# Qwiic_TMF8801.net
KiCad netlist of a schematic drawn in EAGLE
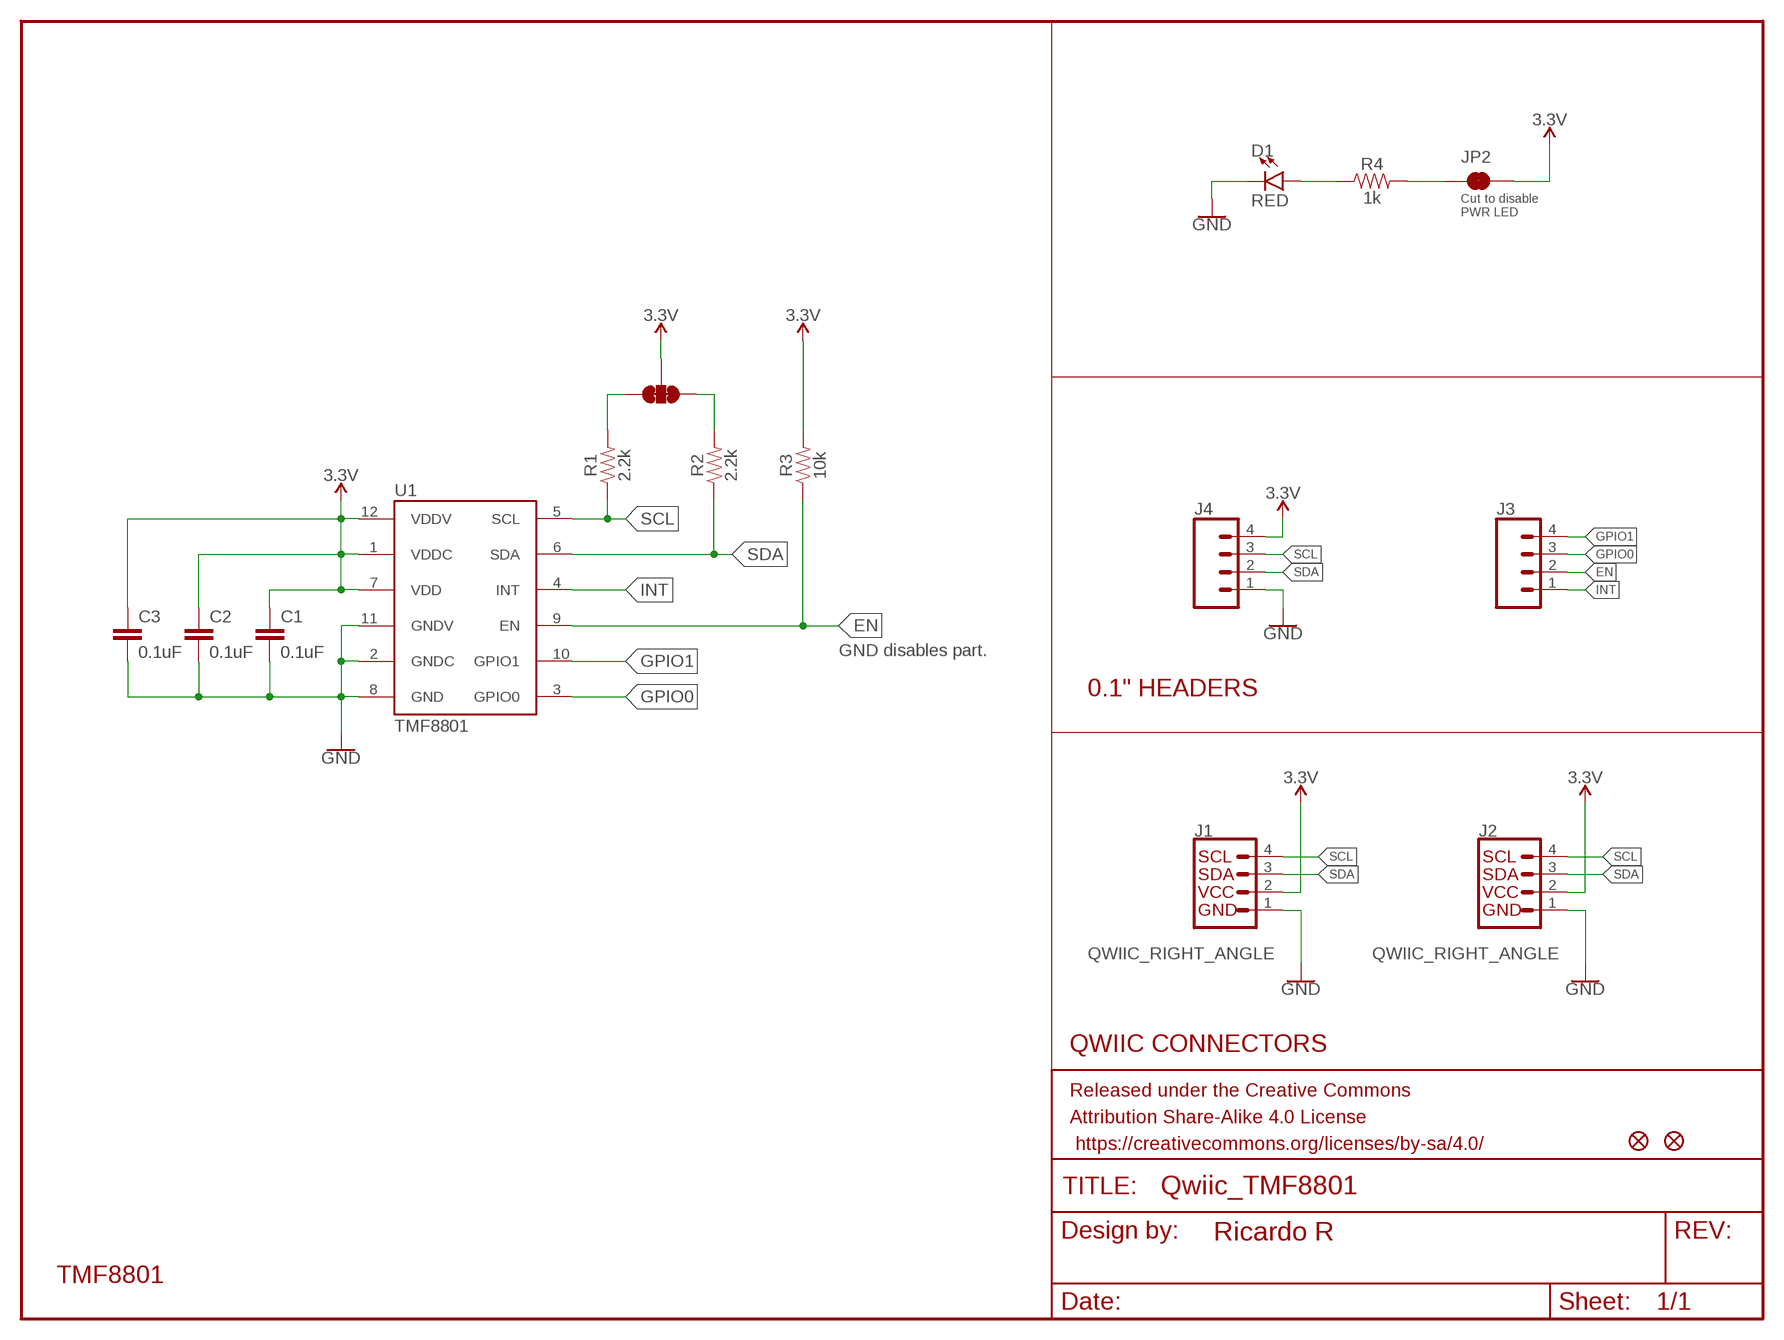
[diagram p0: schematic, sheet 1]

(export (version "E")
  (design (tool "Eeschema 10.0.6"))
  (components
    (comp (ref "C1")
      (value "0.1uF")
      (footprint "eagle-import:0603")
      (libsource (lib "eagle-import") (part "0.1UF-0603-25V-5%"))
    )
    (comp (ref "C2")
      (value "0.1uF")
      (footprint "eagle-import:0603")
      (libsource (lib "eagle-import") (part "0.1UF-0603-25V-5%"))
    )
    (comp (ref "C3")
      (value "0.1uF")
      (footprint "eagle-import:0603")
      (libsource (lib "eagle-import") (part "0.1UF-0603-25V-5%"))
    )
    (comp (ref "D1")
      (value "RED")
      (footprint "eagle-import:LED-0603")
      (libsource (lib "eagle-import") (part "LED-RED0603"))
    )
    (comp (ref "FD1")
      (value "FIDUCIAL1X2")
      (footprint "eagle-import:FIDUCIAL-1X2")
      (libsource (lib "eagle-import") (part "FIDUCIAL1X2"))
    )
    (comp (ref "FD2")
      (value "FIDUCIAL1X2")
      (footprint "eagle-import:FIDUCIAL-1X2")
      (libsource (lib "eagle-import") (part "FIDUCIAL1X2"))
    )
    (comp (ref "FRAME1")
      (value "FRAME-LETTERNO_PACKAGE")
      (footprint "eagle-import:DUMMY")
      (fields (field (name "DESIGNER") "Ricardo R") (field (name "DESIGNER_1") "Ricardo R"))
      (libsource (lib "eagle-import") (part "FRAME-LETTERNO_PACKAGE"))
    )
    (comp (ref "J1")
      (value "QWIIC_RIGHT_ANGLE")
      (footprint "eagle-import:1X04_1MM_RA")
      (libsource (lib "eagle-import") (part "QWIIC_CONNECTORJS-1MM"))
    )
    (comp (ref "J2")
      (value "QWIIC_RIGHT_ANGLE")
      (footprint "eagle-import:1X04_1MM_RA")
      (libsource (lib "eagle-import") (part "QWIIC_CONNECTORJS-1MM"))
    )
    (comp (ref "J3")
      (value "CONN_04")
      (footprint "eagle-import:1X04")
      (libsource (lib "eagle-import") (part "CONN_04"))
    )
    (comp (ref "J4")
      (value "CONN_04")
      (footprint "eagle-import:1X04")
      (libsource (lib "eagle-import") (part "CONN_04"))
    )
    (comp (ref "JP1")
      (value "JUMPER-SMT_3_2-NC_TRACE_SILK")
      (footprint "eagle-import:SMT-JUMPER_3_2-NC_TRACE_SILK")
      (libsource (lib "eagle-import") (part "JUMPER-SMT_3_2-NC_TRACE_SILK"))
    )
    (comp (ref "JP2")
      (value "JUMPER-SMT_2_NC_TRACE_SILK")
      (footprint "eagle-import:SMT-JUMPER_2_NC_TRACE_SILK")
      (libsource (lib "eagle-import") (part "JUMPER-SMT_2_NC_TRACE_SILK"))
    )
    (comp (ref "R1")
      (value "2.2k")
      (footprint "eagle-import:0603")
      (libsource (lib "eagle-import") (part "2.2KOHM-0603-1/10W-1%"))
    )
    (comp (ref "R2")
      (value "2.2k")
      (footprint "eagle-import:0603")
      (libsource (lib "eagle-import") (part "2.2KOHM-0603-1/10W-1%"))
    )
    (comp (ref "R3")
      (value "10k")
      (footprint "eagle-import:0603")
      (libsource (lib "eagle-import") (part "10KOHM-0603-1/10W-1%"))
    )
    (comp (ref "R4")
      (value "1k")
      (footprint "eagle-import:0603")
      (libsource (lib "eagle-import") (part "1KOHM-0603-1/10W-1%"))
    )
    (comp (ref "U1")
      (value "TMF8801")
      (footprint "eagle-import:TMF8801-CUSTOM")
      (libsource (lib "eagle-import") (part "TMF8801TMF8801"))
    )
  )
  (nets
    (net (code "1") (name "3.3V") (class "Default")
      (node (ref "C1") (pin "1") (pinfunction "1_1") (pintype "passive"))
      (node (ref "C2") (pin "1") (pinfunction "1_1") (pintype "passive"))
      (node (ref "C3") (pin "1") (pinfunction "1_1") (pintype "passive"))
      (node (ref "J1") (pin "2") (pinfunction "VCC_2") (pintype "power_in"))
      (node (ref "J2") (pin "2") (pinfunction "VCC_2") (pintype "power_in"))
      (node (ref "J4") (pin "4") (pinfunction "4_4") (pintype "passive"))
      (node (ref "JP1") (pin "2") (pinfunction "2_2") (pintype "passive"))
      (node (ref "JP2") (pin "2") (pinfunction "2_2") (pintype "passive"))
      (node (ref "R3") (pin "2") (pinfunction "2_2") (pintype "passive"))
      (node (ref "U1") (pin "1") (pinfunction "VDDC_1") (pintype "power_in"))
      (node (ref "U1") (pin "12") (pinfunction "VDDV_12") (pintype "power_in"))
      (node (ref "U1") (pin "7") (pinfunction "VDD_7") (pintype "power_in"))
    )
    (net (code "2") (name "EN") (class "Default")
      (node (ref "J3") (pin "2") (pinfunction "2_2") (pintype "passive"))
      (node (ref "R3") (pin "1") (pinfunction "1_1") (pintype "passive"))
      (node (ref "U1") (pin "9") (pinfunction "EN_9") (pintype "input"))
    )
    (net (code "3") (name "GND") (class "Default")
      (node (ref "C1") (pin "2") (pinfunction "2_2") (pintype "passive"))
      (node (ref "C2") (pin "2") (pinfunction "2_2") (pintype "passive"))
      (node (ref "C3") (pin "2") (pinfunction "2_2") (pintype "passive"))
      (node (ref "D1") (pin "C") (pinfunction "C_C") (pintype "passive"))
      (node (ref "J1") (pin "1") (pinfunction "GND_1") (pintype "power_in"))
      (node (ref "J2") (pin "1") (pinfunction "GND_1") (pintype "power_in"))
      (node (ref "J4") (pin "1") (pinfunction "1_1") (pintype "passive"))
      (node (ref "U1") (pin "11") (pinfunction "GNDV_11") (pintype "power_in"))
      (node (ref "U1") (pin "2") (pinfunction "GNDC_2") (pintype "power_in"))
      (node (ref "U1") (pin "8") (pinfunction "GND_8") (pintype "power_in"))
    )
    (net (code "4") (name "GPIO0") (class "Default")
      (node (ref "J3") (pin "3") (pinfunction "3_3") (pintype "passive"))
      (node (ref "U1") (pin "3") (pinfunction "GPIO0_3") (pintype "bidirectional"))
    )
    (net (code "5") (name "GPIO1") (class "Default")
      (node (ref "J3") (pin "4") (pinfunction "4_4") (pintype "passive"))
      (node (ref "U1") (pin "10") (pinfunction "GPIO1_10") (pintype "bidirectional"))
    )
    (net (code "6") (name "INT") (class "Default")
      (node (ref "J3") (pin "1") (pinfunction "1_1") (pintype "passive"))
      (node (ref "U1") (pin "4") (pinfunction "INT_4") (pintype "open_collector"))
    )
    (net (code "7") (name "Net-(D1-PadA)") (class "Default")
      (node (ref "D1") (pin "A") (pinfunction "A_A") (pintype "passive"))
      (node (ref "R4") (pin "1") (pinfunction "1_1") (pintype "passive"))
    )
    (net (code "8") (name "Net-(JP1-Pad1)") (class "Default")
      (node (ref "JP1") (pin "1") (pinfunction "1_1") (pintype "passive"))
      (node (ref "R2") (pin "2") (pinfunction "2_2") (pintype "passive"))
    )
    (net (code "9") (name "Net-(JP1-Pad3)") (class "Default")
      (node (ref "JP1") (pin "3") (pinfunction "3_3") (pintype "passive"))
      (node (ref "R1") (pin "2") (pinfunction "2_2") (pintype "passive"))
    )
    (net (code "10") (name "Net-(JP2-Pad1)") (class "Default")
      (node (ref "JP2") (pin "1") (pinfunction "1_1") (pintype "passive"))
      (node (ref "R4") (pin "2") (pinfunction "2_2") (pintype "passive"))
    )
    (net (code "11") (name "SCL") (class "Default")
      (node (ref "J1") (pin "4") (pinfunction "SCL_4") (pintype "passive"))
      (node (ref "J2") (pin "4") (pinfunction "SCL_4") (pintype "passive"))
      (node (ref "J4") (pin "3") (pinfunction "3_3") (pintype "passive"))
      (node (ref "R1") (pin "1") (pinfunction "1_1") (pintype "passive"))
      (node (ref "U1") (pin "5") (pinfunction "SCL_5") (pintype "bidirectional"))
    )
    (net (code "12") (name "SDA") (class "Default")
      (node (ref "J1") (pin "3") (pinfunction "SDA_3") (pintype "passive"))
      (node (ref "J2") (pin "3") (pinfunction "SDA_3") (pintype "passive"))
      (node (ref "J4") (pin "2") (pinfunction "2_2") (pintype "passive"))
      (node (ref "R2") (pin "1") (pinfunction "1_1") (pintype "passive"))
      (node (ref "U1") (pin "6") (pinfunction "SDA_6") (pintype "bidirectional"))
    )
  )
)
